# SparkFun_Joystick_Shield_Kit.net
KiCad netlist of a schematic drawn in EAGLE
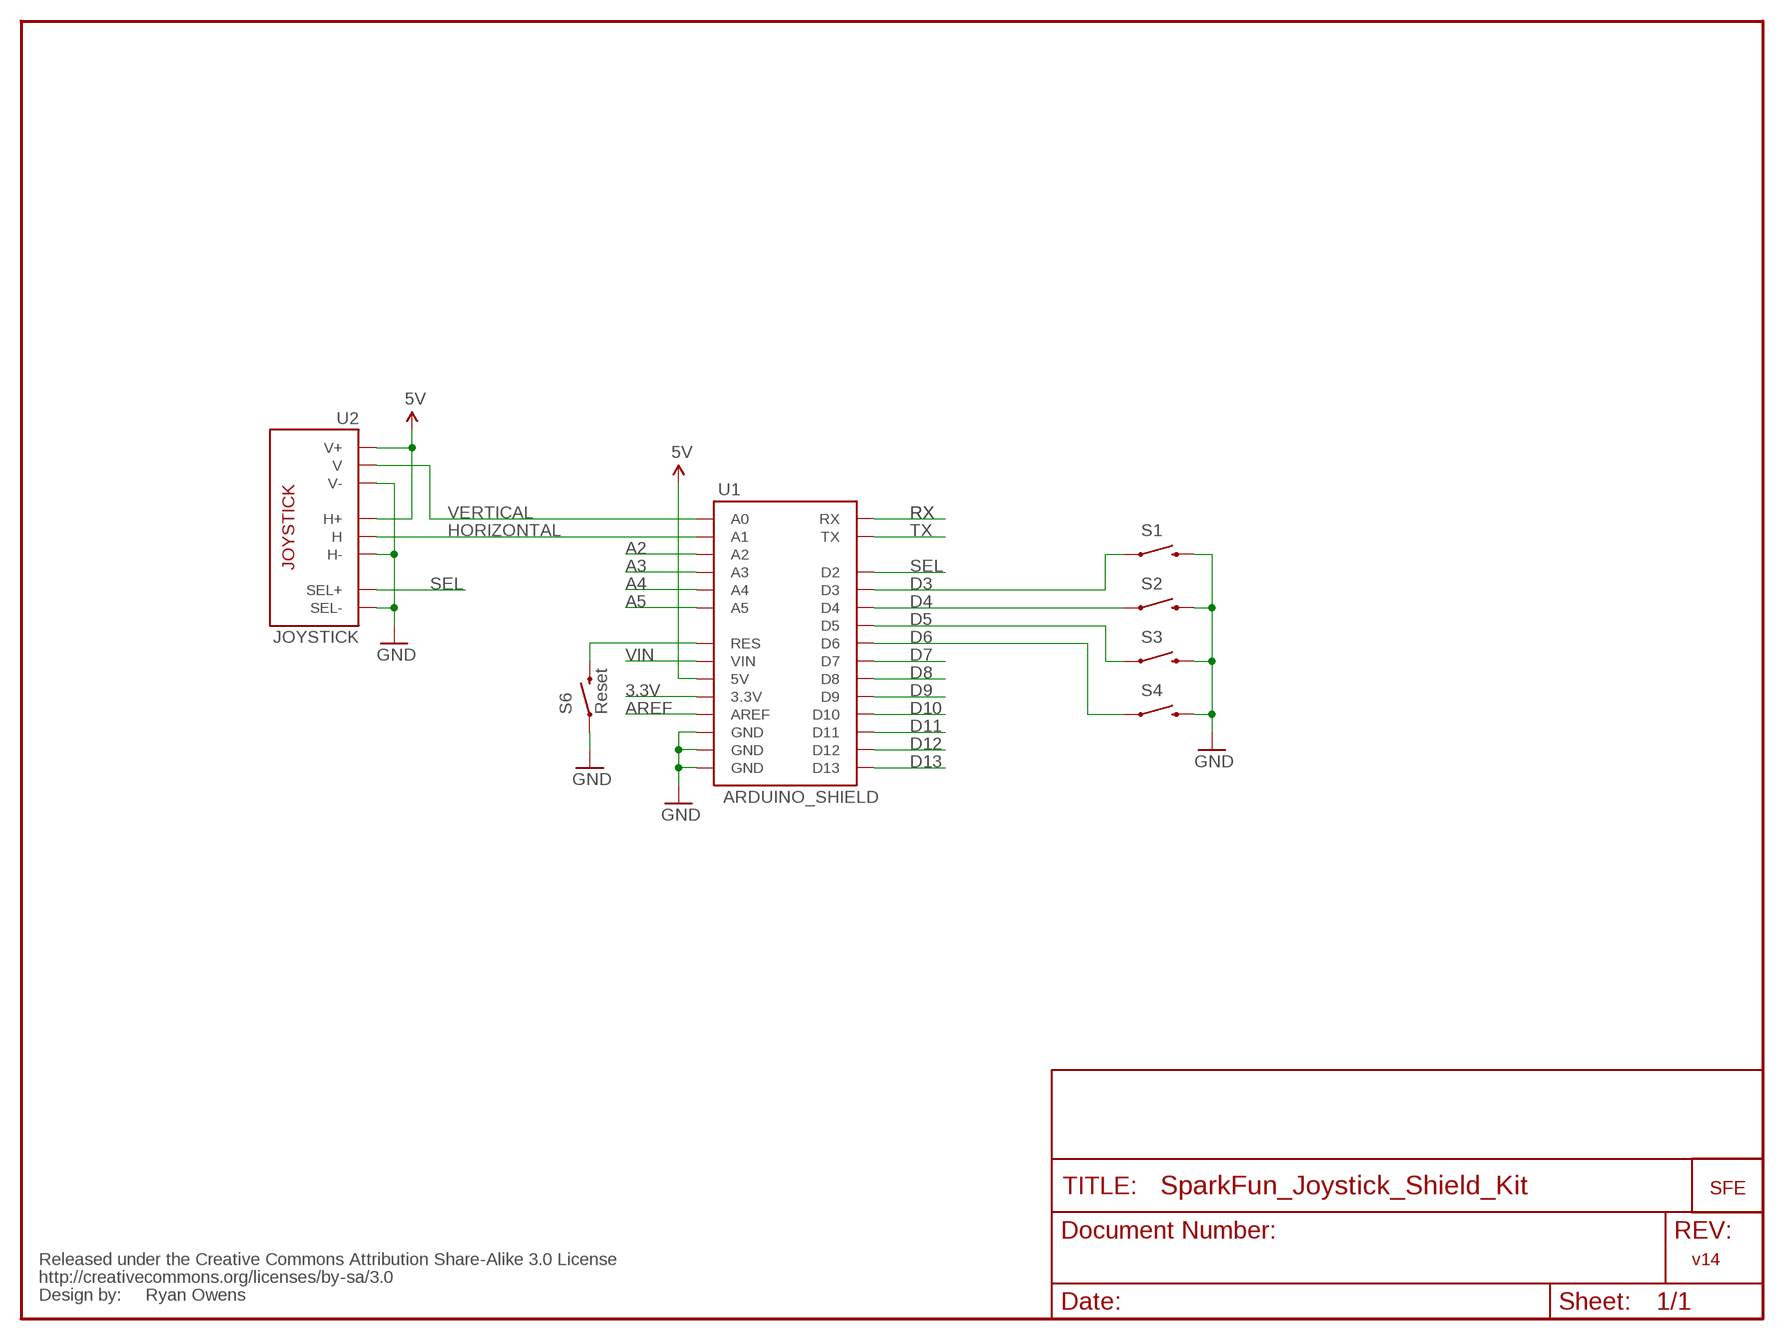
[diagram p0: schematic, sheet 1]

(export (version "E")
  (design (tool "Eeschema 10.0.6"))
  (components
    (comp (ref "JP1")
      (value "LOGO-SFENEW")
      (footprint "eagle-import:SFE-NEW-WEBLOGO")
      (libsource (lib "eagle-import") (part "LOGO-SFENEW"))
    )
    (comp (ref "S1")
      (value "SWITCH-MOMENTARY-212MM")
      (footprint "eagle-import:TACTILE-PTH-12MM")
      (libsource (lib "eagle-import") (part "SWITCH-MOMENTARY-212MM"))
    )
    (comp (ref "S2")
      (value "SWITCH-MOMENTARY-212MM")
      (footprint "eagle-import:TACTILE-PTH-12MM")
      (libsource (lib "eagle-import") (part "SWITCH-MOMENTARY-212MM"))
    )
    (comp (ref "S3")
      (value "SWITCH-MOMENTARY-212MM")
      (footprint "eagle-import:TACTILE-PTH-12MM")
      (libsource (lib "eagle-import") (part "SWITCH-MOMENTARY-212MM"))
    )
    (comp (ref "S4")
      (value "SWITCH-MOMENTARY-212MM")
      (footprint "eagle-import:TACTILE-PTH-12MM")
      (libsource (lib "eagle-import") (part "SWITCH-MOMENTARY-212MM"))
    )
    (comp (ref "S6")
      (value "Reset")
      (footprint "eagle-import:TACTILE-PTH")
      (libsource (lib "eagle-import") (part "SWITCH-MOMENTARY-2PTH"))
    )
    (comp (ref "U$3")
      (value "CREATIVE_COMMONS")
      (footprint "eagle-import:CREATIVE_COMMONS")
      (libsource (lib "eagle-import") (part "CREATIVE_COMMONS"))
    )
    (comp (ref "U1")
      (value "ARDUINO_SHIELD")
      (footprint "eagle-import:DUEMILANOVE_SHIELD")
      (libsource (lib "eagle-import") (part "ARDUINO_SHIELDLABEL"))
    )
    (comp (ref "U2")
      (value "JOYSTICK")
      (footprint "eagle-import:JOYSTICK")
      (libsource (lib "eagle-import") (part "JOYSTICKPTH"))
    )
  )
  (nets
    (net (code "1") (name "/3.3V") (class "Default")
      (node (ref "U1") (pin "3.3V") (pinfunction "3.3V_3.3V") (pintype "bidirectional"))
    )
    (net (code "2") (name "/A2") (class "Default")
      (node (ref "U1") (pin "A2") (pinfunction "A2_A2") (pintype "bidirectional"))
    )
    (net (code "3") (name "/A3") (class "Default")
      (node (ref "U1") (pin "A3") (pinfunction "A3_A3") (pintype "bidirectional"))
    )
    (net (code "4") (name "/A4") (class "Default")
      (node (ref "U1") (pin "A4") (pinfunction "A4_A4") (pintype "bidirectional"))
    )
    (net (code "5") (name "/A5") (class "Default")
      (node (ref "U1") (pin "A5") (pinfunction "A5_A5") (pintype "bidirectional"))
    )
    (net (code "6") (name "/AREF") (class "Default")
      (node (ref "U1") (pin "AREF") (pinfunction "AREF_AREF") (pintype "bidirectional"))
    )
    (net (code "7") (name "/D3") (class "Default")
      (node (ref "S1") (pin "1") (pinfunction "1_1") (pintype "passive"))
      (node (ref "U1") (pin "D3") (pinfunction "D3_D3") (pintype "bidirectional"))
    )
    (net (code "8") (name "/D4") (class "Default")
      (node (ref "S2") (pin "1") (pinfunction "1_1") (pintype "passive"))
      (node (ref "U1") (pin "D4") (pinfunction "D4_D4") (pintype "bidirectional"))
    )
    (net (code "9") (name "/D5") (class "Default")
      (node (ref "S3") (pin "1") (pinfunction "1_1") (pintype "passive"))
      (node (ref "U1") (pin "D5") (pinfunction "D5_D5") (pintype "bidirectional"))
    )
    (net (code "10") (name "/D6") (class "Default")
      (node (ref "S4") (pin "1") (pinfunction "1_1") (pintype "passive"))
      (node (ref "U1") (pin "D6") (pinfunction "D6_D6") (pintype "bidirectional"))
    )
    (net (code "11") (name "/D7") (class "Default")
      (node (ref "U1") (pin "D7") (pinfunction "D7_D7") (pintype "bidirectional"))
    )
    (net (code "12") (name "/D8") (class "Default")
      (node (ref "U1") (pin "D8") (pinfunction "D8_D8") (pintype "bidirectional"))
    )
    (net (code "13") (name "/D9") (class "Default")
      (node (ref "U1") (pin "D9") (pinfunction "D9_D9") (pintype "bidirectional"))
    )
    (net (code "14") (name "/D10") (class "Default")
      (node (ref "U1") (pin "D10") (pinfunction "D10_D10") (pintype "bidirectional"))
    )
    (net (code "15") (name "/D11") (class "Default")
      (node (ref "U1") (pin "D11") (pinfunction "D11_D11") (pintype "bidirectional"))
    )
    (net (code "16") (name "/D12") (class "Default")
      (node (ref "U1") (pin "D12") (pinfunction "D12_D12") (pintype "bidirectional"))
    )
    (net (code "17") (name "/D13") (class "Default")
      (node (ref "U1") (pin "D13") (pinfunction "D13_D13") (pintype "bidirectional"))
    )
    (net (code "18") (name "/HORIZONTAL") (class "Default")
      (node (ref "U1") (pin "A1") (pinfunction "A1_A1") (pintype "bidirectional"))
      (node (ref "U2") (pin "H2") (pinfunction "H_H2") (pintype "bidirectional"))
    )
    (net (code "19") (name "/RX") (class "Default")
      (node (ref "U1") (pin "RX") (pinfunction "RX_RX") (pintype "bidirectional"))
    )
    (net (code "20") (name "/SEL") (class "Default")
      (node (ref "U1") (pin "D2") (pinfunction "D2_D2") (pintype "bidirectional"))
      (node (ref "U2") (pin "B1A") (pinfunction "SEL+_B1A") (pintype "bidirectional"))
    )
    (net (code "21") (name "/TX") (class "Default")
      (node (ref "U1") (pin "TX") (pinfunction "TX_TX") (pintype "bidirectional"))
    )
    (net (code "22") (name "/VERTICAL") (class "Default")
      (node (ref "U1") (pin "A0") (pinfunction "A0_A0") (pintype "bidirectional"))
      (node (ref "U2") (pin "V2") (pinfunction "V_V2") (pintype "bidirectional"))
    )
    (net (code "23") (name "/VIN") (class "Default")
      (node (ref "U1") (pin "VIN") (pinfunction "VIN_VIN") (pintype "bidirectional"))
    )
    (net (code "24") (name "5V") (class "Default")
      (node (ref "U1") (pin "5V") (pinfunction "5V_5V") (pintype "bidirectional"))
      (node (ref "U2") (pin "H1") (pinfunction "H+_H1") (pintype "bidirectional"))
      (node (ref "U2") (pin "V1") (pinfunction "V+_V1") (pintype "bidirectional"))
    )
    (net (code "25") (name "GND") (class "Default")
      (node (ref "S1") (pin "3") (pinfunction "2_3") (pintype "passive"))
      (node (ref "S2") (pin "3") (pinfunction "2_3") (pintype "passive"))
      (node (ref "S3") (pin "3") (pinfunction "2_3") (pintype "passive"))
      (node (ref "S4") (pin "3") (pinfunction "2_3") (pintype "passive"))
      (node (ref "S6") (pin "1") (pinfunction "1_1") (pintype "passive"))
      (node (ref "U1") (pin "GND@0") (pinfunction "GND_GND@0") (pintype "bidirectional"))
      (node (ref "U1") (pin "GND@1") (pinfunction "GND_GND@1") (pintype "bidirectional"))
      (node (ref "U1") (pin "GND@2") (pinfunction "GND_GND@2") (pintype "bidirectional"))
      (node (ref "U2") (pin "B2A") (pinfunction "SEL-_B2A") (pintype "bidirectional"))
      (node (ref "U2") (pin "H3") (pinfunction "H-_H3") (pintype "bidirectional"))
      (node (ref "U2") (pin "V3") (pinfunction "V-_V3") (pintype "bidirectional"))
    )
    (net (code "26") (name "Net-(S6-2)") (class "Default")
      (node (ref "S6") (pin "3") (pinfunction "2_3") (pintype "passive"))
      (node (ref "U1") (pin "RES") (pinfunction "RES_RES") (pintype "bidirectional"))
    )
  )
)
